# coenv_SCH.net
KiCad netlist of a schematic drawn in Altium Designer
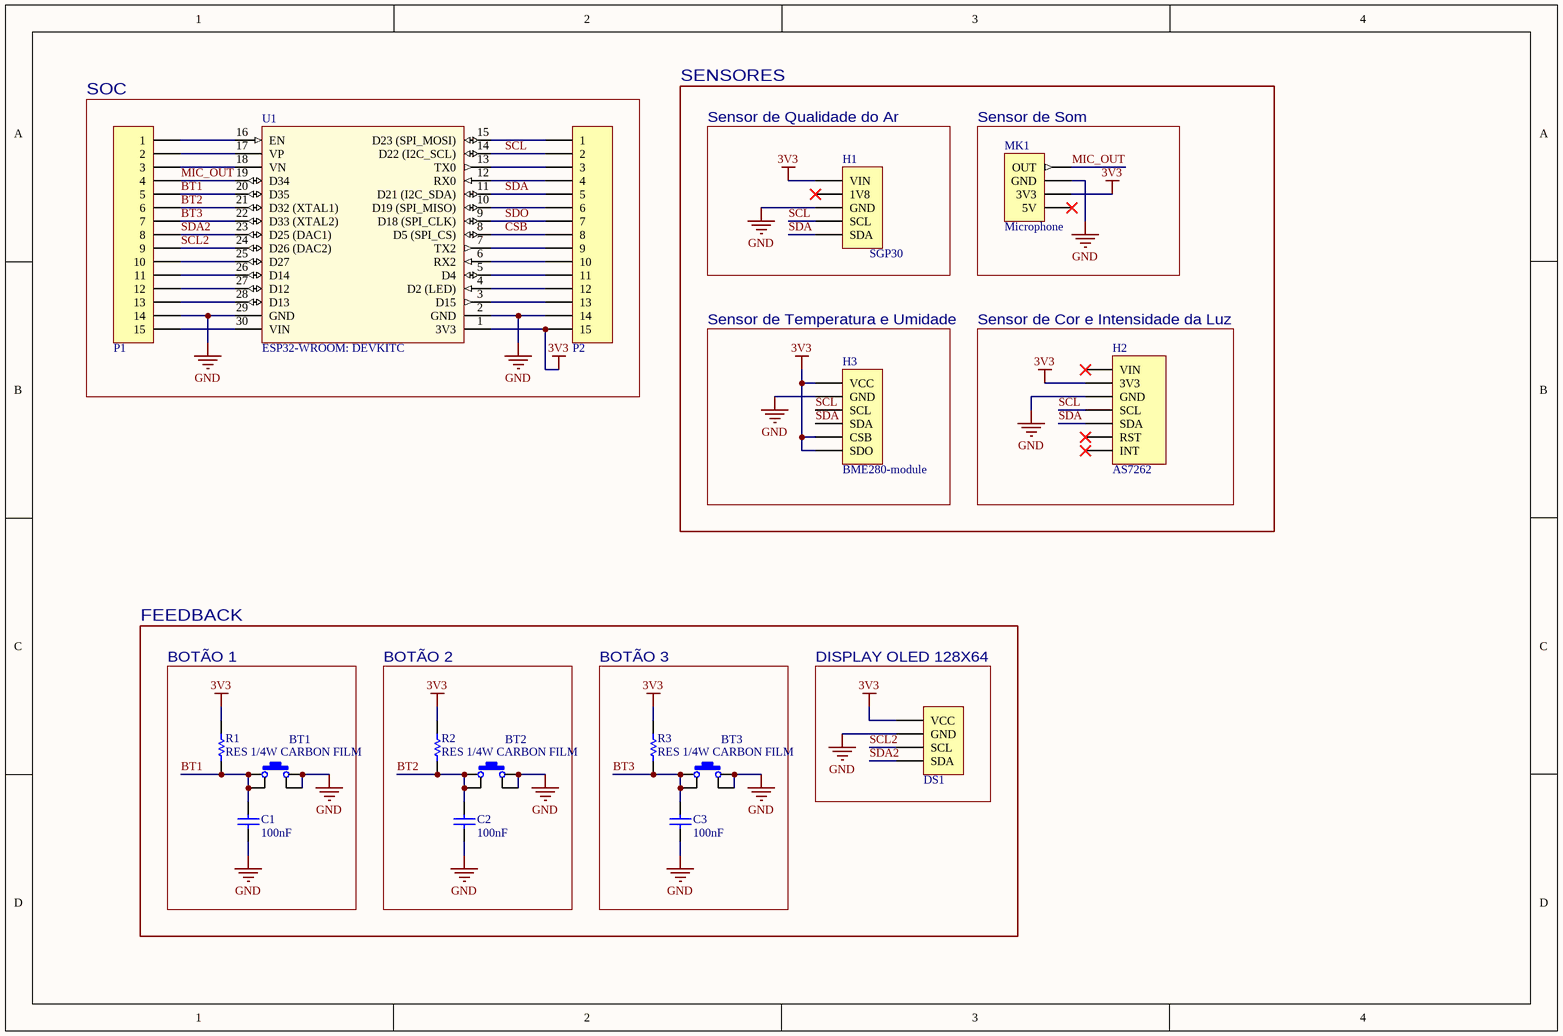
[diagram p0: coenv_SCH.SchDoc]

(export (version "E")
  (design (tool "Eeschema 10.0.6"))
  (components
    (comp (ref "BT1")
      (value "SPST")
      (footprint "TACT SWITCH PHT")
      (description "SWITCH TACTILE SPST-NO 0.05A 24V")
      (fields
        (field (name "MANUFACTURER") "TE Connectivity ALCOSWITCH Switches")
        (field (name "MANUFACTURER PART NUMBER") "FSM2JSMAA")
      )
      (libsource (lib "coenv_SCHLIB") (part "SWITCH TACTILE SPST-NO 0.05A 24V"))
    )
    (comp (ref "BT2")
      (value "SPST")
      (footprint "TACT SWITCH PHT")
      (description "SWITCH TACTILE SPST-NO 0.05A 24V")
      (fields
        (field (name "MANUFACTURER") "TE Connectivity ALCOSWITCH Switches")
        (field (name "MANUFACTURER PART NUMBER") "FSM2JSMAA")
      )
      (libsource (lib "coenv_SCHLIB") (part "SWITCH TACTILE SPST-NO 0.05A 24V"))
    )
    (comp (ref "BT3")
      (value "SPST")
      (footprint "TACT SWITCH PHT")
      (description "SWITCH TACTILE SPST-NO 0.05A 24V")
      (fields
        (field (name "MANUFACTURER") "TE Connectivity ALCOSWITCH Switches")
        (field (name "MANUFACTURER PART NUMBER") "FSM2JSMAA")
      )
      (libsource (lib "coenv_SCHLIB") (part "SWITCH TACTILE SPST-NO 0.05A 24V"))
    )
    (comp (ref "C1")
      (value "100nF")
      (footprint "CAP CER DISK 100NF 50V")
      (description "Multilayer Ceramic Capacitors MLCC - SMD/SMT 0603 0.1uF 16volts X7R 5%")
      (fields
        (field (name "MANUFACTURER") "Vishay / Vitramon")
        (field (name "MANUFACTURER PART NUMBER") "VJ0603Y104JXJPW1BC")
      )
      (libsource (lib "coenv_SCHLIB") (part "CAP CER 0.1UF 16V 5% 0603"))
    )
    (comp (ref "C2")
      (value "100nF")
      (footprint "CAP CER DISK 100NF 50V")
      (description "Multilayer Ceramic Capacitors MLCC - SMD/SMT 0603 0.1uF 16volts X7R 5%")
      (fields
        (field (name "MANUFACTURER") "Vishay / Vitramon")
        (field (name "MANUFACTURER PART NUMBER") "VJ0603Y104JXJPW1BC")
      )
      (libsource (lib "coenv_SCHLIB") (part "CAP CER 0.1UF 16V 5% 0603"))
    )
    (comp (ref "C3")
      (value "100nF")
      (footprint "CAP CER DISK 100NF 50V")
      (description "Multilayer Ceramic Capacitors MLCC - SMD/SMT 0603 0.1uF 16volts X7R 5%")
      (fields
        (field (name "MANUFACTURER") "Vishay / Vitramon")
        (field (name "MANUFACTURER PART NUMBER") "VJ0603Y104JXJPW1BC")
      )
      (libsource (lib "coenv_SCHLIB") (part "CAP CER 0.1UF 16V 5% 0603"))
    )
    (comp (ref "DS1")
      (value "Display OLED")
      (footprint "OLED 128x64 - offset")
      (description "MONOCHROME 1.3 128X64")
      (fields
        (field (name "MANUFACTURER") "Adafruit Industries")
        (field (name "MANUFACTURER PART NUMBER") "938")
      )
      (libsource (lib "coenv_SCHLIB") (part "Display OLED"))
    )
    (comp (ref "H1")
      (value "SGP30")
      (footprint "SGP30 1x5")
      (description "SGP30 AIR QUALITY SENSOR BREAKOU")
      (fields
        (field (name "MANUFACTURER") "Adafruit Industries")
        (field (name "MANUFACTURER PART NUMBER") "3709")
      )
      (libsource (lib "coenv_SCHLIB") (part "SGP30"))
    )
    (comp (ref "H2")
      (value "AS7262")
      (footprint "AS7262")
      (description "Adafruit AS7262 6-Channel Visible Light / Color Sensor Breakout")
      (fields
        (field (name "MANUFACTURER") "Adafruit Industries")
        (field (name "MANUFACTURER PART NUMBER") "3779")
      )
      (libsource (lib "coenv_SCHLIB") (part "AS7262"))
    )
    (comp (ref "H3")
      (value "BME280-module")
      (footprint "BME280 1x6")
      (description "SENSOR HUM/PRESS I2C/SPI BME280")
      (fields
        (field (name "MANUFACTURER") "Adafruit Industries")
        (field (name "MANUFACTURER PART NUMBER") "2652")
      )
      (libsource (lib "coenv_SCHLIB") (part "BME280-module"))
    )
    (comp (ref "MK1")
      (value "Microphone")
      (footprint "microphone module max4466")
      (fields
        (field (name "MANUFACTURER") "Adafruit Industries")
        (field (name "MANUFACTURER PART NUMBER") "1063")
      )
      (libsource (lib "coenv_SCHLIB") (part "Microphone"))
    )
    (comp (ref "P1")
      (value "Header 15")
      (footprint "HDR FEMALE 1x15")
      (description "Header, 15-Pin")
      (fields (field (name "PUBLISHER") "Altium Limited"))
      (libsource (lib "") (part "Header 15_1"))
    )
    (comp (ref "P2")
      (value "Header 15")
      (footprint "HDR FEMALE 1x15")
      (description "Header, 15-Pin")
      (fields (field (name "PUBLISHER") "Altium Limited"))
      (libsource (lib "coenv_SCHLIB") (part "Header 15"))
    )
    (comp (ref "R1")
      (value "RES 1/4W CARBON FILM")
      (footprint "RES 10K 1/4W CARBON FILM")
      (description "RES ? OHM 1/4W 5% CARBON FILM")
      (fields (field (name "MANUFACTURER") "Ty-Ohm") (field (name "MANUFACTURER PART NUMBER") "CR25"))
      (libsource (lib "coenv_SCHLIB") (part "RES 1/4W CARBON FILM"))
    )
    (comp (ref "R2")
      (value "RES 1/4W CARBON FILM")
      (footprint "RES 10K 1/4W CARBON FILM")
      (description "RES ? OHM 1/4W 5% CARBON FILM")
      (fields (field (name "MANUFACTURER") "Ty-Ohm") (field (name "MANUFACTURER PART NUMBER") "CR25"))
      (libsource (lib "coenv_SCHLIB") (part "RES 1/4W CARBON FILM"))
    )
    (comp (ref "R3")
      (value "RES 1/4W CARBON FILM")
      (footprint "RES 10K 1/4W CARBON FILM_STAND")
      (description "RES ? OHM 1/4W 5% CARBON FILM")
      (fields (field (name "MANUFACTURER") "Ty-Ohm") (field (name "MANUFACTURER PART NUMBER") "CR25"))
      (libsource (lib "coenv_SCHLIB") (part "RES 1/4W CARBON FILM"))
    )
    (comp (ref "U1")
      (value "ESP32-DEVKITC")
      (footprint "ESP32-WROOM-devkit")
      (description "EVAL BOARD FOR ESP-WROOM-32")
      (fields (field (name "MANUFACTURER") "Espressif Systems") (field (name "ESP32-WROOM") "DEVKITC"))
      (libsource (lib "coenv_SCHLIB") (part "ESP32-DEVKITC"))
    )
  )
  (nets
    (net (code "1") (name "/BT1") (class "Default")
      (node (ref "BT1") (pin "1") (pinfunction "1_1") (pintype "passive"))
      (node (ref "BT1") (pin "2") (pinfunction "2_2") (pintype "passive"))
      (node (ref "C1") (pin "2") (pinfunction "2_2") (pintype "passive"))
      (node (ref "P1") (pin "5") (pinfunction "5_5") (pintype "passive"))
      (node (ref "R1") (pin "1") (pinfunction "1_1") (pintype "passive"))
      (node (ref "U1") (pin "20") (pinfunction "D35_20") (pintype "bidirectional"))
    )
    (net (code "2") (name "/BT2") (class "Default")
      (node (ref "BT2") (pin "1") (pinfunction "1_1") (pintype "passive"))
      (node (ref "BT2") (pin "2") (pinfunction "2_2") (pintype "passive"))
      (node (ref "C2") (pin "2") (pinfunction "2_2") (pintype "passive"))
      (node (ref "P1") (pin "6") (pinfunction "6_6") (pintype "passive"))
      (node (ref "R2") (pin "1") (pinfunction "1_1") (pintype "passive"))
      (node (ref "U1") (pin "21") (pinfunction "D32_(XTAL1)_21") (pintype "bidirectional"))
    )
    (net (code "3") (name "/BT3") (class "Default")
      (node (ref "BT3") (pin "1") (pinfunction "1_1") (pintype "passive"))
      (node (ref "BT3") (pin "2") (pinfunction "2_2") (pintype "passive"))
      (node (ref "C3") (pin "2") (pinfunction "2_2") (pintype "passive"))
      (node (ref "P1") (pin "7") (pinfunction "7_7") (pintype "passive"))
      (node (ref "R3") (pin "1") (pinfunction "1_1") (pintype "passive"))
      (node (ref "U1") (pin "22") (pinfunction "D33_(XTAL2)_22") (pintype "bidirectional"))
    )
    (net (code "4") (name "/CSB") (class "Default")
      (node (ref "P2") (pin "8") (pinfunction "8_8") (pintype "passive"))
      (node (ref "U1") (pin "8") (pinfunction "D5_(SPI_CS)_8") (pintype "bidirectional"))
    )
    (net (code "5") (name "/MIC_OUT") (class "Default")
      (node (ref "MK1") (pin "4") (pinfunction "OUT_4") (pintype "output"))
      (node (ref "P1") (pin "4") (pinfunction "4_4") (pintype "passive"))
      (node (ref "U1") (pin "19") (pinfunction "D34_19") (pintype "bidirectional"))
    )
    (net (code "6") (name "/SCL") (class "Default")
      (node (ref "H1") (pin "4") (pinfunction "SCL_4") (pintype "passive"))
      (node (ref "H2") (pin "4") (pinfunction "SCL_4") (pintype "passive"))
      (node (ref "H3") (pin "3") (pinfunction "SCL_3") (pintype "passive"))
      (node (ref "P2") (pin "2") (pinfunction "2_2") (pintype "passive"))
      (node (ref "U1") (pin "14") (pinfunction "D22_(I2C_SCL)_14") (pintype "bidirectional"))
    )
    (net (code "7") (name "/SCL2") (class "Default")
      (node (ref "DS1") (pin "3") (pinfunction "SCL_3") (pintype "passive"))
      (node (ref "P1") (pin "9") (pinfunction "9_9") (pintype "passive"))
      (node (ref "U1") (pin "24") (pinfunction "D26_(DAC2)_24") (pintype "bidirectional"))
    )
    (net (code "8") (name "/SDA") (class "Default")
      (node (ref "H1") (pin "5") (pinfunction "SDA_5") (pintype "passive"))
      (node (ref "H2") (pin "5") (pinfunction "SDA_5") (pintype "passive"))
      (node (ref "H3") (pin "4") (pinfunction "SDA_4") (pintype "passive"))
      (node (ref "P2") (pin "5") (pinfunction "5_5") (pintype "passive"))
      (node (ref "U1") (pin "11") (pinfunction "D21_(I2C_SDA)_11") (pintype "bidirectional"))
    )
    (net (code "9") (name "/SDA2") (class "Default")
      (node (ref "DS1") (pin "4") (pinfunction "SDA_4") (pintype "passive"))
      (node (ref "P1") (pin "8") (pinfunction "8_8") (pintype "passive"))
      (node (ref "U1") (pin "23") (pinfunction "D25_(DAC1)_23") (pintype "bidirectional"))
    )
    (net (code "10") (name "/SDO") (class "Default")
      (node (ref "P2") (pin "7") (pinfunction "7_7") (pintype "passive"))
      (node (ref "U1") (pin "9") (pinfunction "D18_(SPI_CLK)_9") (pintype "bidirectional"))
    )
    (net (code "11") (name "3V3") (class "Default")
      (node (ref "DS1") (pin "1") (pinfunction "VCC_1") (pintype "power_in"))
      (node (ref "H1") (pin "1") (pinfunction "VIN_1") (pintype "power_in"))
      (node (ref "H2") (pin "2") (pinfunction "3V3_2") (pintype "power_in"))
      (node (ref "H3") (pin "1") (pinfunction "VCC_1") (pintype "power_in"))
      (node (ref "H3") (pin "5") (pinfunction "CSB_5") (pintype "passive"))
      (node (ref "H3") (pin "6") (pinfunction "SDO_6") (pintype "passive"))
      (node (ref "MK1") (pin "2") (pinfunction "3V3_2") (pintype "power_in"))
      (node (ref "P2") (pin "15") (pinfunction "15_15") (pintype "passive"))
      (node (ref "R1") (pin "2") (pinfunction "2_2") (pintype "passive"))
      (node (ref "R2") (pin "2") (pinfunction "2_2") (pintype "passive"))
      (node (ref "R3") (pin "2") (pinfunction "2_2") (pintype "passive"))
      (node (ref "U1") (pin "1") (pinfunction "3V3_1") (pintype "power_in"))
    )
    (net (code "12") (name "GND") (class "Default")
      (node (ref "BT1") (pin "3") (pinfunction "3_3") (pintype "passive"))
      (node (ref "BT1") (pin "4") (pinfunction "4_4") (pintype "passive"))
      (node (ref "BT2") (pin "3") (pinfunction "3_3") (pintype "passive"))
      (node (ref "BT2") (pin "4") (pinfunction "4_4") (pintype "passive"))
      (node (ref "BT3") (pin "3") (pinfunction "3_3") (pintype "passive"))
      (node (ref "BT3") (pin "4") (pinfunction "4_4") (pintype "passive"))
      (node (ref "C1") (pin "1") (pinfunction "1_1") (pintype "passive"))
      (node (ref "C2") (pin "1") (pinfunction "1_1") (pintype "passive"))
      (node (ref "C3") (pin "1") (pinfunction "1_1") (pintype "passive"))
      (node (ref "DS1") (pin "2") (pinfunction "GND_2") (pintype "power_in"))
      (node (ref "H1") (pin "3") (pinfunction "GND_3") (pintype "power_in"))
      (node (ref "H2") (pin "3") (pinfunction "GND_3") (pintype "power_in"))
      (node (ref "H3") (pin "2") (pinfunction "GND_2") (pintype "open_emitter"))
      (node (ref "MK1") (pin "3") (pinfunction "GND_3") (pintype "power_in"))
      (node (ref "P1") (pin "14") (pinfunction "14_14") (pintype "passive"))
      (node (ref "P2") (pin "14") (pinfunction "14_14") (pintype "passive"))
      (node (ref "U1") (pin "2") (pinfunction "GND_2") (pintype "power_in"))
      (node (ref "U1") (pin "29") (pinfunction "GND_29") (pintype "power_in"))
    )
    (net (code "13") (name "Net-(U1-D2_(LED))") (class "Default")
      (node (ref "P2") (pin "12") (pinfunction "12_12") (pintype "passive"))
      (node (ref "U1") (pin "4") (pinfunction "D2_(LED)_4") (pintype "input"))
    )
    (net (code "14") (name "Net-(U1-D4)") (class "Default")
      (node (ref "P2") (pin "11") (pinfunction "11_11") (pintype "passive"))
      (node (ref "U1") (pin "5") (pinfunction "D4_5") (pintype "bidirectional"))
    )
    (net (code "15") (name "Net-(U1-D12)") (class "Default")
      (node (ref "P1") (pin "12") (pinfunction "12_12") (pintype "passive"))
      (node (ref "U1") (pin "27") (pinfunction "D12_27") (pintype "bidirectional"))
    )
    (net (code "16") (name "Net-(U1-D13)") (class "Default")
      (node (ref "P1") (pin "13") (pinfunction "13_13") (pintype "passive"))
      (node (ref "U1") (pin "28") (pinfunction "D13_28") (pintype "bidirectional"))
    )
    (net (code "17") (name "Net-(U1-D14)") (class "Default")
      (node (ref "P1") (pin "11") (pinfunction "11_11") (pintype "passive"))
      (node (ref "U1") (pin "26") (pinfunction "D14_26") (pintype "bidirectional"))
    )
    (net (code "18") (name "Net-(U1-D15)") (class "Default")
      (node (ref "P2") (pin "13") (pinfunction "13_13") (pintype "passive"))
      (node (ref "U1") (pin "3") (pinfunction "D15_3") (pintype "output"))
    )
    (net (code "19") (name "Net-(U1-D19_(SPI_MISO))") (class "Default")
      (node (ref "P2") (pin "6") (pinfunction "6_6") (pintype "passive"))
      (node (ref "U1") (pin "10") (pinfunction "D19_(SPI_MISO)_10") (pintype "bidirectional"))
    )
    (net (code "20") (name "Net-(U1-D23_(SPI_MOSI))") (class "Default")
      (node (ref "P2") (pin "1") (pinfunction "1_1") (pintype "passive"))
      (node (ref "U1") (pin "15") (pinfunction "D23_(SPI_MOSI)_15") (pintype "bidirectional"))
    )
    (net (code "21") (name "Net-(U1-D27)") (class "Default")
      (node (ref "P1") (pin "10") (pinfunction "10_10") (pintype "passive"))
      (node (ref "U1") (pin "25") (pinfunction "D27_25") (pintype "bidirectional"))
    )
    (net (code "22") (name "Net-(U1-EN)") (class "Default")
      (node (ref "P1") (pin "1") (pinfunction "1_1") (pintype "passive"))
      (node (ref "U1") (pin "16") (pinfunction "EN_16") (pintype "input"))
    )
    (net (code "23") (name "Net-(U1-RX0)") (class "Default")
      (node (ref "P2") (pin "4") (pinfunction "4_4") (pintype "passive"))
      (node (ref "U1") (pin "12") (pinfunction "RX0_12") (pintype "input"))
    )
    (net (code "24") (name "Net-(U1-RX2)") (class "Default")
      (node (ref "P2") (pin "10") (pinfunction "10_10") (pintype "passive"))
      (node (ref "U1") (pin "6") (pinfunction "RX2_6") (pintype "input"))
    )
    (net (code "25") (name "Net-(U1-TX0)") (class "Default")
      (node (ref "P2") (pin "3") (pinfunction "3_3") (pintype "passive"))
      (node (ref "U1") (pin "13") (pinfunction "TX0_13") (pintype "output"))
    )
    (net (code "26") (name "Net-(U1-TX2)") (class "Default")
      (node (ref "P2") (pin "9") (pinfunction "9_9") (pintype "passive"))
      (node (ref "U1") (pin "7") (pinfunction "TX2_7") (pintype "output"))
    )
    (net (code "27") (name "Net-(U1-VIN)") (class "Default")
      (node (ref "P1") (pin "15") (pinfunction "15_15") (pintype "passive"))
      (node (ref "U1") (pin "30") (pinfunction "VIN_30") (pintype "power_in"))
    )
    (net (code "28") (name "Net-(U1-VN)") (class "Default")
      (node (ref "P1") (pin "3") (pinfunction "3_3") (pintype "passive"))
      (node (ref "U1") (pin "18") (pinfunction "VN_18") (pintype "passive"))
    )
    (net (code "29") (name "Net-(U1-VP)") (class "Default")
      (node (ref "P1") (pin "2") (pinfunction "2_2") (pintype "passive"))
      (node (ref "U1") (pin "17") (pinfunction "VP_17") (pintype "passive"))
    )
    (net (code "30") (name "unconnected-(H1-1V8-Pad2)") (class "Default")
      (node (ref "H1") (pin "2") (pinfunction "1V8_2") (pintype "power_in+no_connect"))
    )
    (net (code "31") (name "unconnected-(H2-INT-Pad7)") (class "Default")
      (node (ref "H2") (pin "7") (pinfunction "INT_7") (pintype "passive+no_connect"))
    )
    (net (code "32") (name "unconnected-(H2-RST-Pad6)") (class "Default")
      (node (ref "H2") (pin "6") (pinfunction "RST_6") (pintype "passive+no_connect"))
    )
    (net (code "33") (name "unconnected-(H2-VIN-Pad1)") (class "Default")
      (node (ref "H2") (pin "1") (pinfunction "VIN_1") (pintype "power_in+no_connect"))
    )
    (net (code "34") (name "unconnected-(MK1-5V-Pad1)") (class "Default")
      (node (ref "MK1") (pin "1") (pinfunction "5V_1") (pintype "power_in+no_connect"))
    )
  )
)
